# DisplaySystem_v1.net
KiCad netlist of a schematic drawn in Altium Designer
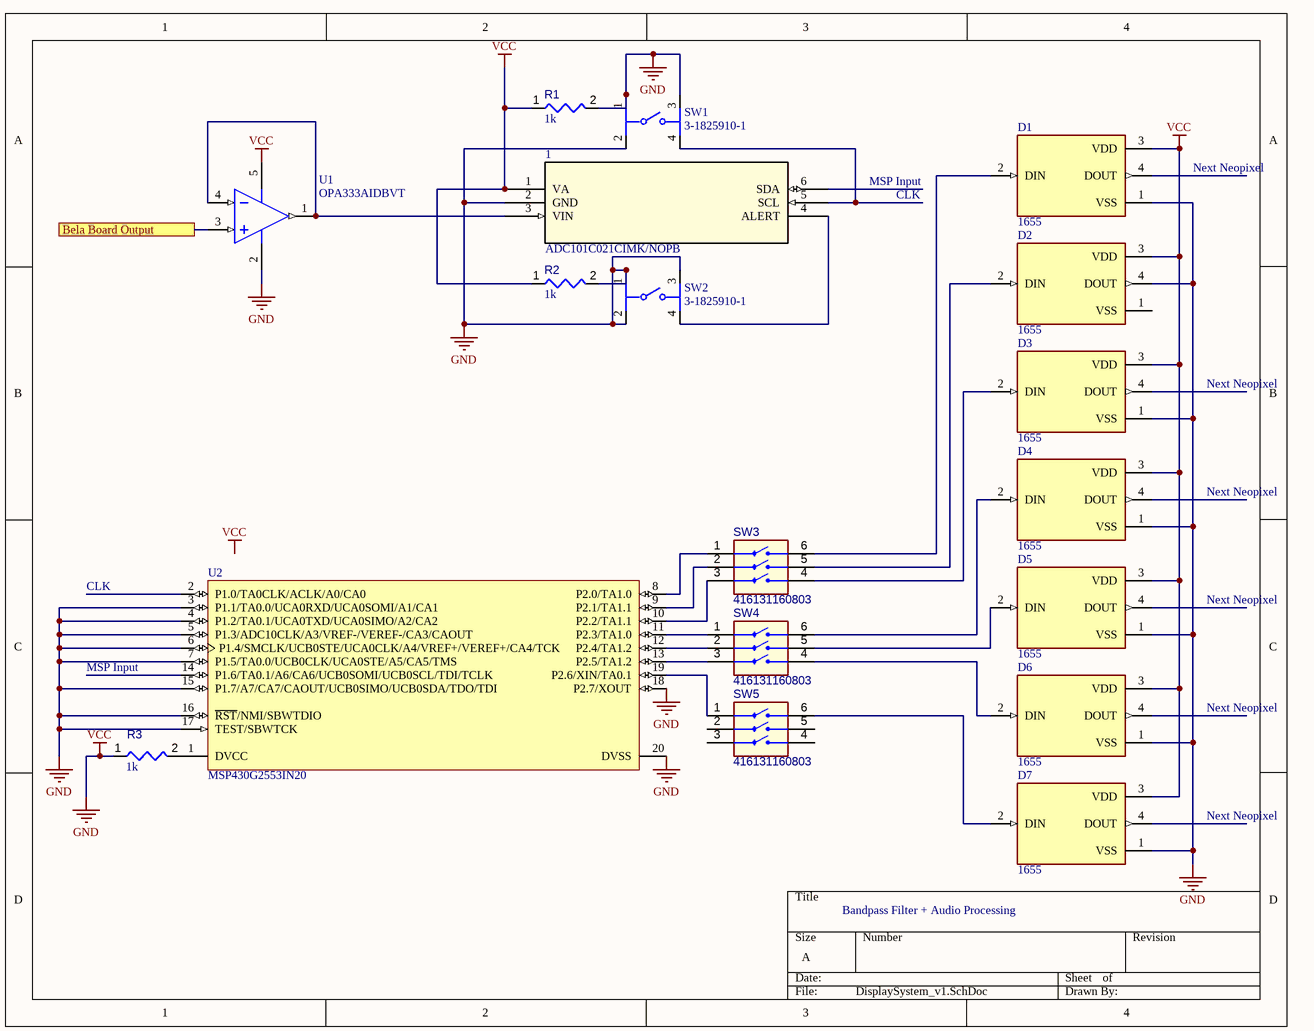
[diagram p0: DisplaySystem_v1.SchDoc]

(export (version "E")
  (design (tool "Eeschema 10.0.6"))
  (components
    (comp (ref "1")
      (value "ADC101C021CIMK/NOPB")
      (footprint "MK06A")
      (description "No Description Available")
      (fields (field (name "COPYRIGHT") "Copyright (C) 2022 Ultra Librarian. All rights reserved."))
      (libsource (lib "ADC101C021CIMK&slash_NOPB") (part "ADC101C021CIMK/NOPB"))
    )
    (comp (ref "D1")
      (value "1655")
      (footprint "SnapEDApcb:LED_1655")
      (fields (field (name "MF") "Adafruit Industries"))
      (libsource (lib "SnapEDAsch") (part "1655"))
    )
    (comp (ref "D2")
      (value "1655")
      (footprint "SnapEDApcb:LED_1655")
      (fields (field (name "MF") "Adafruit Industries"))
      (libsource (lib "SnapEDAsch") (part "1655"))
    )
    (comp (ref "D3")
      (value "1655")
      (footprint "SnapEDApcb:LED_1655")
      (fields (field (name "MF") "Adafruit Industries"))
      (libsource (lib "SnapEDAsch") (part "1655"))
    )
    (comp (ref "D4")
      (value "1655")
      (footprint "SnapEDApcb:LED_1655")
      (fields (field (name "MF") "Adafruit Industries"))
      (libsource (lib "SnapEDAsch") (part "1655"))
    )
    (comp (ref "D5")
      (value "1655")
      (footprint "SnapEDApcb:LED_1655")
      (fields (field (name "MF") "Adafruit Industries"))
      (libsource (lib "SnapEDAsch") (part "1655"))
    )
    (comp (ref "D6")
      (value "1655")
      (footprint "SnapEDApcb:LED_1655")
      (fields (field (name "MF") "Adafruit Industries"))
      (libsource (lib "SnapEDAsch") (part "1655"))
    )
    (comp (ref "D7")
      (value "1655")
      (footprint "SnapEDApcb:LED_1655")
      (fields (field (name "MF") "Adafruit Industries"))
      (libsource (lib "SnapEDAsch") (part "1655"))
    )
    (comp (ref "R1")
      (value "1k")
      (footprint "RESC0402(1005)_L")
      (description "Chip Resistor, 2,2 Ohms, +/-5 %, 63 mW, -55 to 155 degC, 0402")
      (fields (field (name "POWER") "63mW") (field (name "TOLERANCE") "5%"))
      (libsource (lib "University of California, Davis") (part "RES-2"))
    )
    (comp (ref "R2")
      (value "1k")
      (footprint "RESC0402(1005)_L")
      (description "Chip Resistor, 2,2 Ohms, +/-5 %, 63 mW, -55 to 155 degC, 0402")
      (fields (field (name "POWER") "63mW") (field (name "TOLERANCE") "5%"))
      (libsource (lib "University of California, Davis") (part "RES-2"))
    )
    (comp (ref "R3")
      (value "1k")
      (footprint "RESC0402(1005)_L")
      (description "Chip Resistor, 2,2 Ohms, +/-5 %, 63 mW, -55 to 155 degC, 0402")
      (fields (field (name "POWER") "63mW") (field (name "TOLERANCE") "5%"))
      (libsource (lib "University of California, Davis") (part "RES-2"))
    )
    (comp (ref "SW1")
      (value "3-1825910-1")
      (footprint "FP-3-1825910-1-MFG")
      (description "Switch Tactile OFF (ON) SPST Round Button PC Pins 0.05A 24VDC 100000Cycles 1.57N Thru-Hole")
      (fields (field (name "MANUFACTURER") "TE Connectivity"))
      (libsource (lib "Altium Content Vault") (part "b8895f3f4cefb76e1819d2863dba89b"))
    )
    (comp (ref "SW2")
      (value "3-1825910-1")
      (footprint "FP-3-1825910-1-MFG")
      (description "Switch Tactile OFF (ON) SPST Round Button PC Pins 0.05A 24VDC 100000Cycles 1.57N Thru-Hole")
      (fields (field (name "MANUFACTURER") "TE Connectivity"))
      (libsource (lib "Altium Content Vault") (part "b8895f3f4cefb76e1819d2863dba89b"))
    )
    (comp (ref "SW3")
      (value "416131160803")
      (footprint "416131160803")
      (description "WS-DISV 1.27 mm small compact SMD Dip Switch with top tape")
      (libsource (lib "University of California, Davis") (part "CMP-00567-2"))
    )
    (comp (ref "SW4")
      (value "416131160803")
      (footprint "416131160803")
      (description "WS-DISV 1.27 mm small compact SMD Dip Switch with top tape")
      (libsource (lib "University of California, Davis") (part "CMP-00567-2"))
    )
    (comp (ref "SW5")
      (value "416131160803")
      (footprint "416131160803")
      (description "WS-DISV 1.27 mm small compact SMD Dip Switch with top tape")
      (libsource (lib "University of California, Davis") (part "CMP-00567-2"))
    )
    (comp (ref "U1")
      (value "OPA333AIDBVT")
      (footprint "DBV0005A_M")
      (fields (field (name "MANUFACTURER") "Texas Instruments (TI)"))
      (libsource (lib "University of California, Davis") (part "TI-OPA333DBV5"))
    )
    (comp (ref "U2")
      (value "MSP430G2553IN20")
      (footprint "N0020A")
      (fields (field (name "MANUFACTURER") "Texas Instruments"))
      (libsource (lib "EE_Emerge_SkillsProject") (part "CMP-0365-00184-2"))
    )
  )
  (nets
    (net (code "1") (name "/Bela Board Output") (class "Default")
      (node (ref "U1") (pin "3") (pinfunction "+IN_3") (pintype "input"))
    )
    (net (code "2") (name "GND") (class "Default")
      (node (ref "1") (pin "1") (pinfunction "VA_1") (pintype "power_in"))
      (node (ref "1") (pin "2") (pinfunction "GND_2") (pintype "power_in"))
      (node (ref "D1") (pin "1") (pinfunction "VSS_1") (pintype "power_in"))
      (node (ref "D1") (pin "3") (pinfunction "VDD_3") (pintype "power_in"))
      (node (ref "D2") (pin "3") (pinfunction "VDD_3") (pintype "power_in"))
      (node (ref "D2") (pin "4") (pinfunction "DOUT_4") (pintype "output"))
      (node (ref "D3") (pin "1") (pinfunction "VSS_1") (pintype "power_in"))
      (node (ref "D3") (pin "3") (pinfunction "VDD_3") (pintype "power_in"))
      (node (ref "D4") (pin "1") (pinfunction "VSS_1") (pintype "power_in"))
      (node (ref "D4") (pin "3") (pinfunction "VDD_3") (pintype "power_in"))
      (node (ref "D5") (pin "1") (pinfunction "VSS_1") (pintype "power_in"))
      (node (ref "D5") (pin "3") (pinfunction "VDD_3") (pintype "power_in"))
      (node (ref "D6") (pin "1") (pinfunction "VSS_1") (pintype "power_in"))
      (node (ref "D6") (pin "3") (pinfunction "VDD_3") (pintype "power_in"))
      (node (ref "D7") (pin "1") (pinfunction "VSS_1") (pintype "power_in"))
      (node (ref "D7") (pin "3") (pinfunction "VDD_3") (pintype "power_in"))
      (node (ref "R1") (pin "1") (pinfunction "1_1") (pintype "passive"))
      (node (ref "R1") (pin "2") (pinfunction "2_2") (pintype "passive"))
      (node (ref "R2") (pin "1") (pinfunction "1_1") (pintype "passive"))
      (node (ref "R2") (pin "2") (pinfunction "2_2") (pintype "passive"))
      (node (ref "R3") (pin "1") (pinfunction "1_1") (pintype "passive"))
      (node (ref "SW1") (pin "1") (pinfunction "1_1") (pintype "passive"))
      (node (ref "SW1") (pin "2") (pinfunction "2_2") (pintype "passive"))
      (node (ref "SW1") (pin "3") (pinfunction "3_3") (pintype "passive"))
      (node (ref "SW2") (pin "1") (pinfunction "1_1") (pintype "passive"))
      (node (ref "SW2") (pin "2") (pinfunction "2_2") (pintype "passive"))
      (node (ref "SW2") (pin "3") (pinfunction "3_3") (pintype "passive"))
      (node (ref "U1") (pin "2") (pinfunction "V-_2") (pintype "power_in"))
      (node (ref "U1") (pin "5") (pinfunction "V+_5") (pintype "power_in"))
      (node (ref "U2") (pin "15") (pinfunction "P1.7/A7/CA7/CAOUT/UCB0SIMO/UCB0SDA/TDO/TDI_15") (pintype "bidirectional"))
      (node (ref "U2") (pin "16") (pinfunction "~{RST}/NMI/SBWTDIO_16") (pintype "bidirectional"))
      (node (ref "U2") (pin "17") (pinfunction "TEST/SBWTCK_17") (pintype "input"))
      (node (ref "U2") (pin "18") (pinfunction "P2.7/XOUT_18") (pintype "bidirectional"))
      (node (ref "U2") (pin "20") (pinfunction "DVSS_20") (pintype "power_in"))
      (node (ref "U2") (pin "3") (pinfunction "P1.1/TA0.0/UCA0RXD/UCA0SOMI/A1/CA1_3") (pintype "bidirectional"))
      (node (ref "U2") (pin "4") (pinfunction "P1.2/TA0.1/UCA0TXD/UCA0SIMO/A2/CA2_4") (pintype "bidirectional"))
      (node (ref "U2") (pin "5") (pinfunction "P1.3/ADC10CLK/A3/VREF-/VEREF-/CA3/CAOUT_5") (pintype "bidirectional"))
      (node (ref "U2") (pin "6") (pinfunction "P1.4/SMCLK/UCB0STE/UCA0CLK/A4/VREF+/VEREF+/CA4/TCK_6") (pintype "bidirectional"))
      (node (ref "U2") (pin "7") (pinfunction "P1.5/TA0.0/UCB0CLK/UCA0STE/A5/CA5/TMS_7") (pintype "bidirectional"))
    )
    (net (code "3") (name "Net-(1-ALERT)") (class "Default")
      (node (ref "1") (pin "4") (pinfunction "ALERT_4") (pintype "passive"))
      (node (ref "SW2") (pin "4") (pinfunction "4_4") (pintype "passive"))
    )
    (net (code "4") (name "Net-(1-SCL)") (class "Default")
      (node (ref "1") (pin "5") (pinfunction "SCL_5") (pintype "input"))
      (node (ref "SW1") (pin "4") (pinfunction "4_4") (pintype "passive"))
    )
    (net (code "5") (name "Net-(1-VIN)") (class "Default")
      (node (ref "1") (pin "3") (pinfunction "VIN_3") (pintype "input"))
      (node (ref "U1") (pin "1") (pinfunction "OUT_1") (pintype "output"))
      (node (ref "U1") (pin "4") (pinfunction "-IN_4") (pintype "input"))
    )
    (net (code "6") (name "Net-(D1-DIN)") (class "Default")
      (node (ref "D1") (pin "2") (pinfunction "DIN_2") (pintype "input"))
      (node (ref "SW3") (pin "6") (pinfunction "6_6") (pintype "passive"))
    )
    (net (code "7") (name "Net-(D2-DIN)") (class "Default")
      (node (ref "D2") (pin "2") (pinfunction "DIN_2") (pintype "input"))
      (node (ref "SW3") (pin "5") (pinfunction "5_5") (pintype "passive"))
    )
    (net (code "8") (name "Net-(D3-DIN)") (class "Default")
      (node (ref "D3") (pin "2") (pinfunction "DIN_2") (pintype "input"))
      (node (ref "SW3") (pin "4") (pinfunction "4_4") (pintype "passive"))
    )
    (net (code "9") (name "Net-(D4-DIN)") (class "Default")
      (node (ref "D4") (pin "2") (pinfunction "DIN_2") (pintype "input"))
      (node (ref "SW4") (pin "6") (pinfunction "6_6") (pintype "passive"))
    )
    (net (code "10") (name "Net-(D5-DIN)") (class "Default")
      (node (ref "D5") (pin "2") (pinfunction "DIN_2") (pintype "input"))
      (node (ref "SW4") (pin "5") (pinfunction "5_5") (pintype "passive"))
    )
    (net (code "11") (name "Net-(D6-DIN)") (class "Default")
      (node (ref "D6") (pin "2") (pinfunction "DIN_2") (pintype "input"))
      (node (ref "SW4") (pin "4") (pinfunction "4_4") (pintype "passive"))
    )
    (net (code "12") (name "Net-(D7-DIN)") (class "Default")
      (node (ref "D7") (pin "2") (pinfunction "DIN_2") (pintype "input"))
      (node (ref "SW5") (pin "6") (pinfunction "6_6") (pintype "passive"))
    )
    (net (code "13") (name "Net-(U2-DVCC)") (class "Default")
      (node (ref "R3") (pin "2") (pinfunction "2_2") (pintype "passive"))
      (node (ref "U2") (pin "1") (pinfunction "DVCC_1") (pintype "power_in"))
    )
    (net (code "14") (name "Net-(U2-P2.0{slash}TA1.0)") (class "Default")
      (node (ref "SW3") (pin "1") (pinfunction "1_1") (pintype "passive"))
      (node (ref "U2") (pin "8") (pinfunction "P2.0/TA1.0_8") (pintype "bidirectional"))
    )
    (net (code "15") (name "Net-(U2-P2.1{slash}TA1.1)") (class "Default")
      (node (ref "SW3") (pin "2") (pinfunction "2_2") (pintype "passive"))
      (node (ref "U2") (pin "9") (pinfunction "P2.1/TA1.1_9") (pintype "bidirectional"))
    )
    (net (code "16") (name "Net-(U2-P2.2{slash}TA1.1)") (class "Default")
      (node (ref "SW3") (pin "3") (pinfunction "3_3") (pintype "passive"))
      (node (ref "U2") (pin "10") (pinfunction "P2.2/TA1.1_10") (pintype "bidirectional"))
    )
    (net (code "17") (name "Net-(U2-P2.3{slash}TA1.0)") (class "Default")
      (node (ref "SW4") (pin "1") (pinfunction "1_1") (pintype "passive"))
      (node (ref "U2") (pin "11") (pinfunction "P2.3/TA1.0_11") (pintype "bidirectional"))
    )
    (net (code "18") (name "Net-(U2-P2.4{slash}TA1.2)") (class "Default")
      (node (ref "SW4") (pin "2") (pinfunction "2_2") (pintype "passive"))
      (node (ref "U2") (pin "12") (pinfunction "P2.4/TA1.2_12") (pintype "bidirectional"))
    )
    (net (code "19") (name "Net-(U2-P2.5{slash}TA1.2)") (class "Default")
      (node (ref "SW4") (pin "3") (pinfunction "3_3") (pintype "passive"))
      (node (ref "U2") (pin "13") (pinfunction "P2.5/TA1.2_13") (pintype "bidirectional"))
    )
    (net (code "20") (name "Net-(U2-P2.6{slash}XIN{slash}TA0.1)") (class "Default")
      (node (ref "SW5") (pin "1") (pinfunction "1_1") (pintype "passive"))
      (node (ref "U2") (pin "19") (pinfunction "P2.6/XIN/TA0.1_19") (pintype "bidirectional"))
    )
    (net (code "21") (name "unconnected-(1-SDA-Pad6)") (class "Default")
      (node (ref "1") (pin "6") (pinfunction "SDA_6") (pintype "bidirectional"))
    )
    (net (code "22") (name "unconnected-(D1-DOUT-Pad4)") (class "Default")
      (node (ref "D1") (pin "4") (pinfunction "DOUT_4") (pintype "output"))
    )
    (net (code "23") (name "unconnected-(D2-VSS-Pad1)") (class "Default")
      (node (ref "D2") (pin "1") (pinfunction "VSS_1") (pintype "power_in"))
    )
    (net (code "24") (name "unconnected-(D3-DOUT-Pad4)") (class "Default")
      (node (ref "D3") (pin "4") (pinfunction "DOUT_4") (pintype "output"))
    )
    (net (code "25") (name "unconnected-(D4-DOUT-Pad4)") (class "Default")
      (node (ref "D4") (pin "4") (pinfunction "DOUT_4") (pintype "output"))
    )
    (net (code "26") (name "unconnected-(D5-DOUT-Pad4)") (class "Default")
      (node (ref "D5") (pin "4") (pinfunction "DOUT_4") (pintype "output"))
    )
    (net (code "27") (name "unconnected-(D6-DOUT-Pad4)") (class "Default")
      (node (ref "D6") (pin "4") (pinfunction "DOUT_4") (pintype "output"))
    )
    (net (code "28") (name "unconnected-(D7-DOUT-Pad4)") (class "Default")
      (node (ref "D7") (pin "4") (pinfunction "DOUT_4") (pintype "output"))
    )
    (net (code "29") (name "unconnected-(SW5-Pad2)") (class "Default")
      (node (ref "SW5") (pin "2") (pinfunction "2_2") (pintype "passive"))
    )
    (net (code "30") (name "unconnected-(SW5-Pad3)") (class "Default")
      (node (ref "SW5") (pin "3") (pinfunction "3_3") (pintype "passive"))
    )
    (net (code "31") (name "unconnected-(SW5-Pad4)") (class "Default")
      (node (ref "SW5") (pin "4") (pinfunction "4_4") (pintype "passive"))
    )
    (net (code "32") (name "unconnected-(SW5-Pad5)") (class "Default")
      (node (ref "SW5") (pin "5") (pinfunction "5_5") (pintype "passive"))
    )
    (net (code "33") (name "unconnected-(U2-P1.0{slash}TA0CLK{slash}ACLK{slash}A0{slash}CA0-Pad2)") (class "Default")
      (node (ref "U2") (pin "2") (pinfunction "P1.0/TA0CLK/ACLK/A0/CA0_2") (pintype "bidirectional"))
    )
    (net (code "34") (name "unconnected-(U2-P1.6{slash}TA0.1{slash}A6{slash}CA6{slash}UCB0SOMI{slash}UCB0SCL{slash}TDI{slash}TCLK-Pad14)") (class "Default")
      (node (ref "U2") (pin "14") (pinfunction "P1.6/TA0.1/A6/CA6/UCB0SOMI/UCB0SCL/TDI/TCLK_14") (pintype "bidirectional"))
    )
  )
)
